# Breadboard_Power_Supply_-_SMD.net
KiCad netlist of a schematic drawn in EAGLE
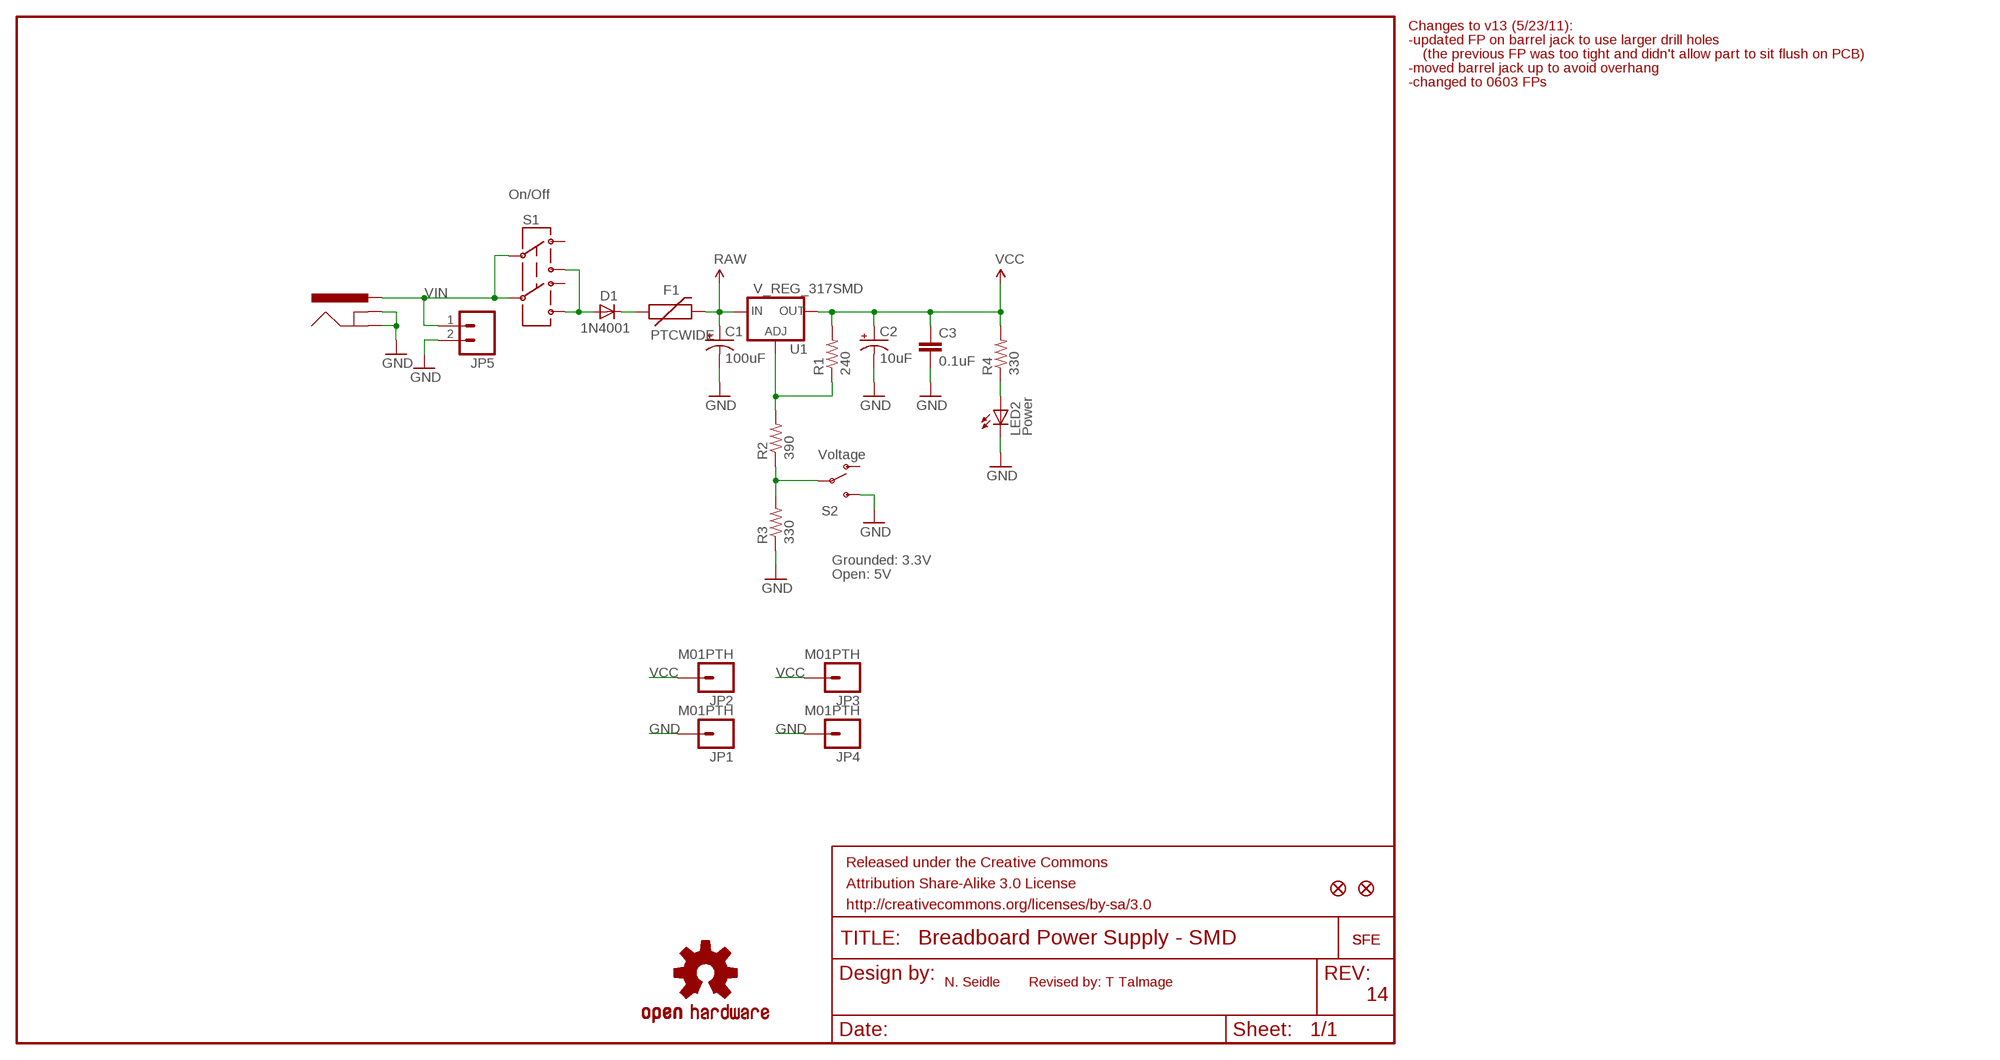
[diagram p0: schematic, sheet 1]

(export (version "E")
  (design (tool "Eeschema 10.0.6"))
  (components
    (comp (ref "C1")
      (value "100uF")
      (footprint "eagle-import:EIA7343")
      (libsource (lib "eagle-import") (part "CAP_POL7343"))
    )
    (comp (ref "C2")
      (value "10uF")
      (footprint "eagle-import:EIA3216")
      (libsource (lib "eagle-import") (part "CAP_POL1206"))
    )
    (comp (ref "C3")
      (value "0.1uF")
      (footprint "eagle-import:0603-CAP")
      (libsource (lib "eagle-import") (part "CAP0603-CAP"))
    )
    (comp (ref "D1")
      (value "1N4001")
      (footprint "eagle-import:SMA-DIODE-TYLERALT1")
      (libsource (lib "eagle-import") (part "DIODESMA-TYLERALT1"))
    )
    (comp (ref "F1")
      (value "PTCWIDE")
      (footprint "eagle-import:PTC-1206-WIDE")
      (libsource (lib "eagle-import") (part "PTCWIDE"))
    )
    (comp (ref "FRAME1")
      (value "FRAME-LETTER")
      (footprint "eagle-import:CREATIVE_COMMONS")
      (libsource (lib "eagle-import") (part "FRAME-LETTER"))
    )
    (comp (ref "J1")
      (value "POWER_JACKTYLERALT1")
      (footprint "eagle-import:POWER_JACK_SMD_TYLERALT1")
      (libsource (lib "eagle-import") (part "POWER_JACKTYLERALT1"))
    )
    (comp (ref "JP1")
      (value "M01PTH")
      (footprint "eagle-import:1X01")
      (libsource (lib "eagle-import") (part "M01PTH"))
    )
    (comp (ref "JP2")
      (value "M01PTH")
      (footprint "eagle-import:1X01")
      (libsource (lib "eagle-import") (part "M01PTH"))
    )
    (comp (ref "JP3")
      (value "M01PTH")
      (footprint "eagle-import:1X01")
      (libsource (lib "eagle-import") (part "M01PTH"))
    )
    (comp (ref "JP4")
      (value "M01PTH")
      (footprint "eagle-import:1X01")
      (libsource (lib "eagle-import") (part "M01PTH"))
    )
    (comp (ref "JP5")
      (value "M02PTH")
      (footprint "eagle-import:1X02")
      (libsource (lib "eagle-import") (part "M02PTH"))
    )
    (comp (ref "LED2")
      (value "Power")
      (footprint "eagle-import:LED-1206")
      (libsource (lib "eagle-import") (part "LED1206"))
    )
    (comp (ref "LOGO1")
      (value "OSHW-LOGOS")
      (footprint "eagle-import:OSHW-LOGO-S")
      (libsource (lib "eagle-import") (part "OSHW-LOGOS"))
    )
    (comp (ref "R1")
      (value "240")
      (footprint "eagle-import:0603-RES")
      (libsource (lib "eagle-import") (part "RESISTOR0603-RES"))
    )
    (comp (ref "R2")
      (value "390")
      (footprint "eagle-import:0603-RES")
      (libsource (lib "eagle-import") (part "RESISTOR0603-RES"))
    )
    (comp (ref "R3")
      (value "330")
      (footprint "eagle-import:0603-RES")
      (libsource (lib "eagle-import") (part "RESISTOR0603-RES"))
    )
    (comp (ref "R4")
      (value "330")
      (footprint "eagle-import:0603-RES")
      (libsource (lib "eagle-import") (part "RESISTOR0603-RES"))
    )
    (comp (ref "S1")
      (value "On/Off")
      (footprint "eagle-import:AYZ0202")
      (libsource (lib "eagle-import") (part "AYZ0202"))
    )
    (comp (ref "S2")
      (value "Voltage")
      (footprint "eagle-import:AYZ0202")
      (libsource (lib "eagle-import") (part "SWITCH-SPSTSMD"))
    )
    (comp (ref "U$1")
      (value "LOGO-SFESK")
      (footprint "eagle-import:SFE-LOGO-FLAME")
      (libsource (lib "eagle-import") (part "LOGO-SFESK"))
    )
    (comp (ref "U$2")
      (value "LOGO-SFENEW")
      (footprint "eagle-import:SFE-NEW-WEBLOGO")
      (libsource (lib "eagle-import") (part "LOGO-SFENEW"))
    )
    (comp (ref "U$3")
      (value "FIDUCIAL1X2")
      (footprint "eagle-import:FIDUCIAL-1X2")
      (libsource (lib "eagle-import") (part "FIDUCIAL1X2"))
    )
    (comp (ref "U$4")
      (value "FIDUCIAL1X2")
      (footprint "eagle-import:FIDUCIAL-1X2")
      (libsource (lib "eagle-import") (part "FIDUCIAL1X2"))
    )
    (comp (ref "U1")
      (value "V_REG_317SMD")
      (footprint "eagle-import:SOT223")
      (libsource (lib "eagle-import") (part "V_REG_317SMD"))
    )
  )
  (nets
    (net (code "1") (name "/VIN") (class "Default")
      (node (ref "J1") (pin "VIN0") (pinfunction "PWR_VIN0") (pintype "bidirectional"))
      (node (ref "JP5") (pin "1") (pinfunction "1_1") (pintype "passive"))
      (node (ref "S1") (pin "2") (pinfunction "2_2") (pintype "bidirectional"))
      (node (ref "S1") (pin "5") (pinfunction "5_5") (pintype "bidirectional"))
    )
    (net (code "2") (name "GND") (class "Default")
      (node (ref "C1") (pin "C") (pinfunction "-_C") (pintype "passive"))
      (node (ref "C2") (pin "C") (pinfunction "-_C") (pintype "passive"))
      (node (ref "C3") (pin "2") (pinfunction "2_2") (pintype "passive"))
      (node (ref "J1") (pin "GND") (pinfunction "GNDBREAK_GND") (pintype "bidirectional"))
      (node (ref "J1") (pin "P$4") (pinfunction "GND_P$4") (pintype "bidirectional"))
      (node (ref "JP1") (pin "1") (pinfunction "1_1") (pintype "passive"))
      (node (ref "JP4") (pin "1") (pinfunction "1_1") (pintype "passive"))
      (node (ref "JP5") (pin "2") (pinfunction "2_2") (pintype "passive"))
      (node (ref "LED2") (pin "C") (pinfunction "C_C") (pintype "passive"))
      (node (ref "R3") (pin "1") (pinfunction "1_1") (pintype "passive"))
      (node (ref "S2") (pin "3") (pinfunction "S_3") (pintype "passive"))
    )
    (net (code "3") (name "Net-(D1-PadC)") (class "Default")
      (node (ref "D1") (pin "C") (pinfunction "C_C") (pintype "passive"))
      (node (ref "F1") (pin "1") (pinfunction "1_1") (pintype "bidirectional"))
    )
    (net (code "4") (name "Net-(LED2-PadA)") (class "Default")
      (node (ref "LED2") (pin "A") (pinfunction "A_A") (pintype "passive"))
      (node (ref "R4") (pin "1") (pinfunction "1_1") (pintype "passive"))
    )
    (net (code "5") (name "Net-(S1-3)") (class "Default")
      (node (ref "D1") (pin "A") (pinfunction "A_A") (pintype "passive"))
      (node (ref "S1") (pin "1") (pinfunction "3_1") (pintype "bidirectional"))
      (node (ref "S1") (pin "4") (pinfunction "6_4") (pintype "bidirectional"))
    )
    (net (code "6") (name "Net-(S2-P)") (class "Default")
      (node (ref "R2") (pin "1") (pinfunction "1_1") (pintype "passive"))
      (node (ref "R3") (pin "2") (pinfunction "2_2") (pintype "passive"))
      (node (ref "S2") (pin "2") (pinfunction "P_2") (pintype "passive"))
    )
    (net (code "7") (name "Net-(U1-ADJ)") (class "Default")
      (node (ref "R1") (pin "1") (pinfunction "1_1") (pintype "passive"))
      (node (ref "R2") (pin "2") (pinfunction "2_2") (pintype "passive"))
      (node (ref "U1") (pin "1") (pinfunction "ADJ_1") (pintype "input"))
    )
    (net (code "8") (name "RAW") (class "Default")
      (node (ref "C1") (pin "A") (pinfunction "+_A") (pintype "passive"))
      (node (ref "F1") (pin "2") (pinfunction "2_2") (pintype "bidirectional"))
      (node (ref "U1") (pin "3") (pinfunction "IN_3") (pintype "input"))
    )
    (net (code "9") (name "VCC") (class "Default")
      (node (ref "C2") (pin "A") (pinfunction "+_A") (pintype "passive"))
      (node (ref "C3") (pin "1") (pinfunction "1_1") (pintype "passive"))
      (node (ref "JP2") (pin "1") (pinfunction "1_1") (pintype "passive"))
      (node (ref "JP3") (pin "1") (pinfunction "1_1") (pintype "passive"))
      (node (ref "R1") (pin "2") (pinfunction "2_2") (pintype "passive"))
      (node (ref "R4") (pin "2") (pinfunction "2_2") (pintype "passive"))
      (node (ref "U1") (pin "2") (pinfunction "OUT_2") (pintype "output"))
    )
    (net (code "10") (name "unconnected-(S1-1-Pad3)") (class "Default")
      (node (ref "S1") (pin "3") (pinfunction "1_3") (pintype "bidirectional"))
    )
    (net (code "11") (name "unconnected-(S1-4-Pad6)") (class "Default")
      (node (ref "S1") (pin "6") (pinfunction "4_6") (pintype "bidirectional"))
    )
    (net (code "12") (name "unconnected-(S2-O-Pad1)") (class "Default")
      (node (ref "S2") (pin "1") (pinfunction "O_1") (pintype "passive"))
    )
  )
)
